# LCD.net
KiCad netlist of a schematic drawn in Altium Designer
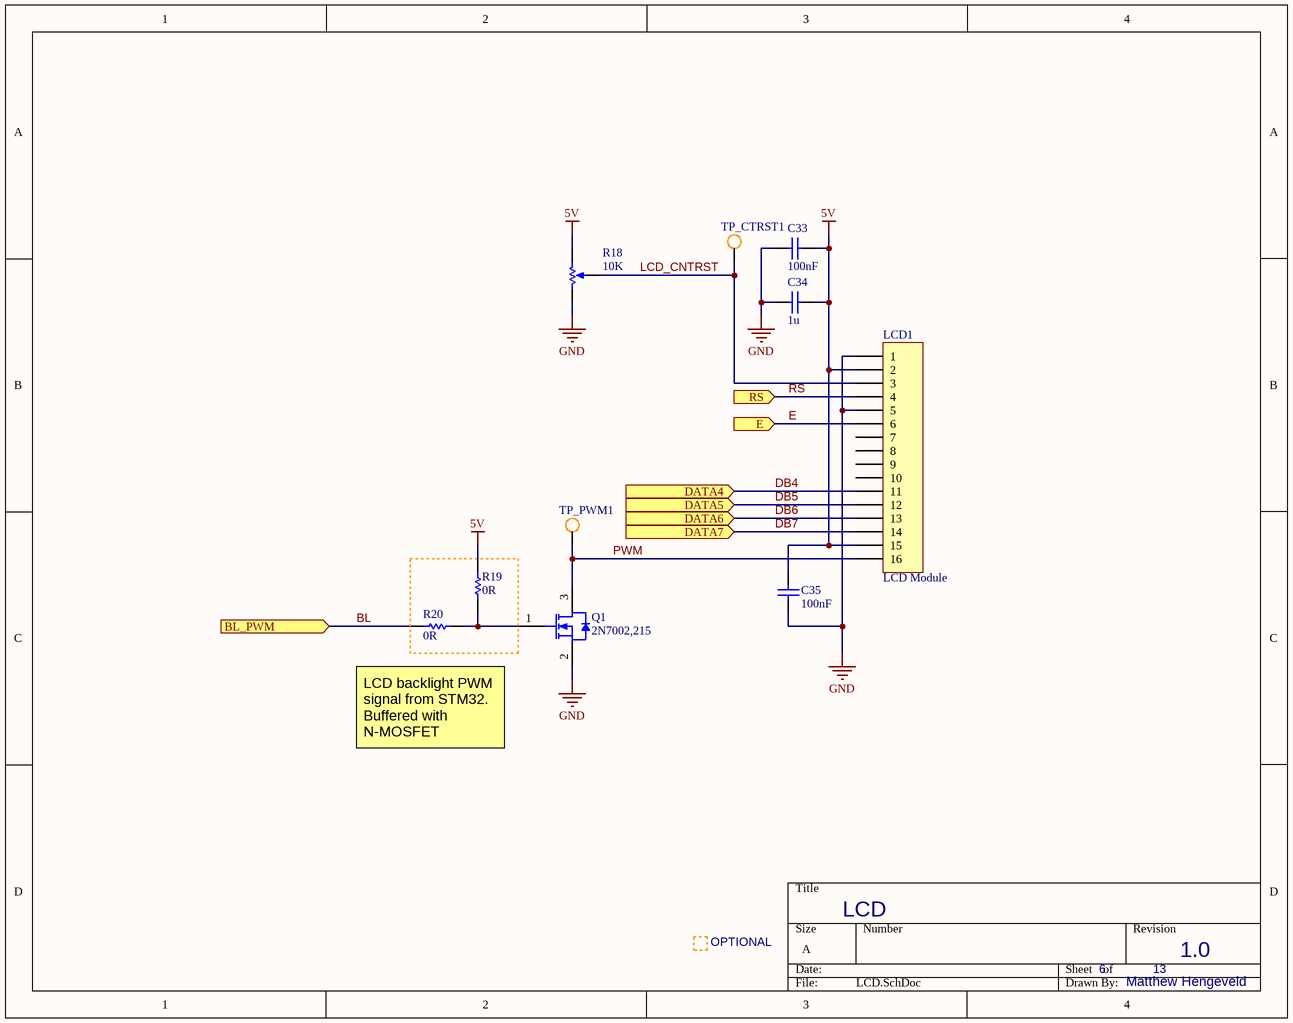
[diagram p0: LCD.SchDoc]

(export (version "E")
  (design (tool "Eeschema 10.0.6"))
  (components
    (comp (ref "C33")
      (value "100nF")
      (footprint "CAPC1608X92X38LL15T08")
      (fields (field (name "PART NUMBER") "VJ0603Y104KNXAO") (field (name "MANUFACTURER") "Vitramon"))
      (libsource (lib "Altium Content Vault") (part "CAP"))
    )
    (comp (ref "C34")
      (value "1u")
      (footprint "CAPC2013X94X50LL20T25")
      (fields
        (field (name "PART NUMBER") "08055C104K4T2A")
        (field (name "MANUFACTURER") "AVX Interconnect / Elco")
      )
      (libsource (lib "Altium Content Vault") (part "CAP"))
    )
    (comp (ref "C35")
      (value "100nF")
      (footprint "CAPC1608X92X38LL15T08")
      (fields (field (name "PART NUMBER") "VJ0603Y104KNXAO") (field (name "MANUFACTURER") "Vitramon"))
      (libsource (lib "Altium Content Vault") (part "CAP"))
    )
    (comp (ref "LCD1")
      (value "LCD Module")
      (footprint "LCD Module")
      (description "Header, 16-Pin")
      (fields (field (name "PUBLISHER") "Altium Limited"))
      (libsource (lib "Hengeveld") (part "LCD Module"))
    )
    (comp (ref "Q1")
      (value "2N7002,215")
      (footprint "NXP-SOT23_L")
      (description "N-Channel Trench MOSFET, 60 V, 0.3 A, 3-Pin SOT23, Tape and Reel")
      (fields (field (name "MANUFACTURER") "NXP Semiconductors"))
      (libsource (lib "Altium Content Vault") (part "NXP-NMOS-GSD-3_B"))
    )
    (comp (ref "R18")
      (value "10K")
      (footprint "BOUR-3266W-3_V")
      (description "Square Trimpot Trimming Potentiometer, 100 KOhm, 0.25 W, -55 to 125 degC, 3-Pin THD, RoHS, Tube")
      (fields (field (name "TOLERANCE") "+/-10%") (field (name "MANUFACTURER") "Bourns"))
      (libsource (lib "Altium Content Vault") (part "BOUR-POT-3"))
    )
    (comp (ref "R19")
      (value "0R")
      (footprint "RESC1609X55X30LL10T20")
      (fields (field (name "PART NUMBER") "CRCW06030000Z0EA") (field (name "MANUFACTURER") "Vishay Dale"))
      (libsource (lib "Altium Content Vault") (part "RES"))
    )
    (comp (ref "R20")
      (value "0R")
      (footprint "RESC1609X55X30LL10T20")
      (fields (field (name "PART NUMBER") "CRCW06030000Z0EA") (field (name "MANUFACTURER") "Vishay Dale"))
      (libsource (lib "Altium Content Vault") (part "RES"))
    )
    (comp (ref "TP_CTRST1")
      (value "Test point")
      (footprint "SMD Test Hook")
      (libsource (lib "Hengeveld") (part "Test Point"))
    )
    (comp (ref "TP_PWM1")
      (value "Test point")
      (footprint "SMD Test Hook")
      (libsource (lib "Hengeveld") (part "Test Point"))
    )
  )
  (nets
    (net (code "1") (name "/BL") (class "Default")
      (node (ref "R20") (pin "2") (pinfunction "2_2") (pintype "passive"))
    )
    (net (code "2") (name "/DB4") (class "Default")
      (node (ref "LCD1") (pin "11") (pinfunction "11_11") (pintype "passive"))
    )
    (net (code "3") (name "/DB5") (class "Default")
      (node (ref "LCD1") (pin "12") (pinfunction "12_12") (pintype "passive"))
    )
    (net (code "4") (name "/DB6") (class "Default")
      (node (ref "LCD1") (pin "13") (pinfunction "13_13") (pintype "passive"))
    )
    (net (code "5") (name "/DB7") (class "Default")
      (node (ref "LCD1") (pin "14") (pinfunction "14_14") (pintype "passive"))
    )
    (net (code "6") (name "/E") (class "Default")
      (node (ref "LCD1") (pin "6") (pinfunction "6_6") (pintype "passive"))
    )
    (net (code "7") (name "/LCD_CNTRST") (class "Default")
      (node (ref "LCD1") (pin "3") (pinfunction "3_3") (pintype "passive"))
      (node (ref "R18") (pin "2") (pinfunction "WIPER_2") (pintype "passive"))
      (node (ref "TP_CTRST1") (pin "1") (pinfunction "point_1") (pintype "passive"))
    )
    (net (code "8") (name "/PWM") (class "Default")
      (node (ref "LCD1") (pin "16") (pinfunction "16_16") (pintype "passive"))
      (node (ref "Q1") (pin "3") (pinfunction "D_3") (pintype "passive"))
      (node (ref "TP_PWM1") (pin "1") (pinfunction "point_1") (pintype "passive"))
    )
    (net (code "9") (name "/RS") (class "Default")
      (node (ref "LCD1") (pin "4") (pinfunction "4_4") (pintype "passive"))
    )
    (net (code "10") (name "5V") (class "Default")
      (node (ref "C33") (pin "1") (pinfunction "1_1") (pintype "passive"))
      (node (ref "C34") (pin "1") (pinfunction "1_1") (pintype "passive"))
      (node (ref "C35") (pin "2") (pinfunction "2_2") (pintype "passive"))
      (node (ref "LCD1") (pin "15") (pinfunction "15_15") (pintype "passive"))
      (node (ref "LCD1") (pin "2") (pinfunction "2_2") (pintype "passive"))
      (node (ref "R18") (pin "1") (pinfunction "CCW_1") (pintype "passive"))
      (node (ref "R19") (pin "2") (pinfunction "2_2") (pintype "passive"))
    )
    (net (code "11") (name "GND") (class "Default")
      (node (ref "C33") (pin "2") (pinfunction "2_2") (pintype "passive"))
      (node (ref "C34") (pin "2") (pinfunction "2_2") (pintype "passive"))
      (node (ref "C35") (pin "1") (pinfunction "1_1") (pintype "passive"))
      (node (ref "LCD1") (pin "1") (pinfunction "1_1") (pintype "passive"))
      (node (ref "LCD1") (pin "5") (pinfunction "5_5") (pintype "passive"))
      (node (ref "Q1") (pin "2") (pinfunction "S_2") (pintype "passive"))
      (node (ref "R18") (pin "3") (pinfunction "CW_3") (pintype "passive"))
    )
    (net (code "12") (name "Net-(Q1-G)") (class "Default")
      (node (ref "Q1") (pin "1") (pinfunction "G_1") (pintype "passive"))
      (node (ref "R19") (pin "1") (pinfunction "1_1") (pintype "passive"))
      (node (ref "R20") (pin "1") (pinfunction "1_1") (pintype "passive"))
    )
    (net (code "13") (name "unconnected-(LCD1-Pad7)") (class "Default")
      (node (ref "LCD1") (pin "7") (pinfunction "7_7") (pintype "passive"))
    )
    (net (code "14") (name "unconnected-(LCD1-Pad8)") (class "Default")
      (node (ref "LCD1") (pin "8") (pinfunction "8_8") (pintype "passive"))
    )
    (net (code "15") (name "unconnected-(LCD1-Pad9)") (class "Default")
      (node (ref "LCD1") (pin "9") (pinfunction "9_9") (pintype "passive"))
    )
    (net (code "16") (name "unconnected-(LCD1-Pad10)") (class "Default")
      (node (ref "LCD1") (pin "10") (pinfunction "10_10") (pintype "passive"))
    )
  )
)
